# ModuleManHinhLCD1602.net
KiCad netlist of a schematic drawn in Altium Designer
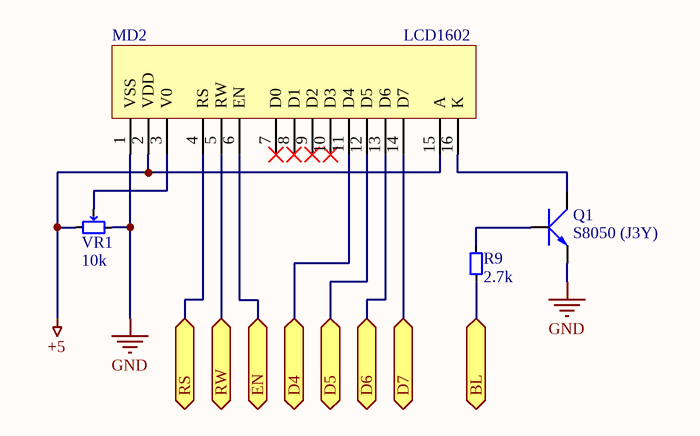
[diagram p0: ModuleManHinhLCD1602.SchDoc]

(export (version "E")
  (design (tool "Eeschema 10.0.6"))
  (components
    (comp (ref "MD2")
      (value "LCD1602")
      (footprint "LCD1602-A")
      (description "Module Man Hinh LCD1602")
      (libsource (lib "Module") (part "LCD1602"))
    )
    (comp (ref "Q1")
      (value "S8050 (J3Y)")
      (footprint "SOT23")
      (description "Transistor NPN 0.5A")
      (libsource (lib "phatvu1294_Lib") (part "S8050 (J3Y)"))
    )
    (comp (ref "R9")
      (value "2.7k")
      (footprint "R-0805")
      (description "Cac Loai Dien Tro")
      (libsource (lib "phatvu1294_Lib") (part "RES"))
    )
    (comp (ref "VR1")
      (value "10k")
      (footprint "VR-ADJ-3362P")
      (description "Cac Loai Bien Tro")
      (libsource (lib "phatvu1294_Lib") (part "VRES"))
    )
  )
  (nets
    (net (code "1") (name "+5") (class "Default")
      (node (ref "MD2") (pin "15") (pinfunction "A_15") (pintype "passive"))
      (node (ref "MD2") (pin "2") (pinfunction "VDD_2") (pintype "passive"))
      (node (ref "VR1") (pin "3") (pinfunction "3_3") (pintype "passive"))
    )
    (net (code "2") (name "/BL") (class "Default")
      (node (ref "R9") (pin "1") (pinfunction "1_1") (pintype "passive"))
    )
    (net (code "3") (name "/D4") (class "Default")
      (node (ref "MD2") (pin "11") (pinfunction "D4_11") (pintype "passive"))
    )
    (net (code "4") (name "/D5") (class "Default")
      (node (ref "MD2") (pin "12") (pinfunction "D5_12") (pintype "passive"))
    )
    (net (code "5") (name "/D6") (class "Default")
      (node (ref "MD2") (pin "13") (pinfunction "D6_13") (pintype "passive"))
    )
    (net (code "6") (name "/D7") (class "Default")
      (node (ref "MD2") (pin "14") (pinfunction "D7_14") (pintype "passive"))
    )
    (net (code "7") (name "/EN") (class "Default")
      (node (ref "MD2") (pin "6") (pinfunction "EN_6") (pintype "passive"))
    )
    (net (code "8") (name "/RS") (class "Default")
      (node (ref "MD2") (pin "4") (pinfunction "RS_4") (pintype "passive"))
    )
    (net (code "9") (name "/RW") (class "Default")
      (node (ref "MD2") (pin "5") (pinfunction "RW_5") (pintype "passive"))
    )
    (net (code "10") (name "GND") (class "Default")
      (node (ref "MD2") (pin "1") (pinfunction "VSS_1") (pintype "passive"))
      (node (ref "Q1") (pin "2") (pinfunction "E_2") (pintype "passive"))
      (node (ref "VR1") (pin "1") (pinfunction "1_1") (pintype "passive"))
    )
    (net (code "11") (name "Net-(MD2-K)") (class "Default")
      (node (ref "MD2") (pin "16") (pinfunction "K_16") (pintype "passive"))
      (node (ref "Q1") (pin "3") (pinfunction "C_3") (pintype "passive"))
    )
    (net (code "12") (name "Net-(MD2-V0)") (class "Default")
      (node (ref "MD2") (pin "3") (pinfunction "V0_3") (pintype "passive"))
      (node (ref "VR1") (pin "2") (pinfunction "2_2") (pintype "passive"))
    )
    (net (code "13") (name "Net-(Q1-B)") (class "Default")
      (node (ref "Q1") (pin "1") (pinfunction "B_1") (pintype "passive"))
      (node (ref "R9") (pin "2") (pinfunction "2_2") (pintype "passive"))
    )
    (net (code "14") (name "unconnected-(MD2-D0-Pad7)") (class "Default")
      (node (ref "MD2") (pin "7") (pinfunction "D0_7") (pintype "passive+no_connect"))
    )
    (net (code "15") (name "unconnected-(MD2-D1-Pad8)") (class "Default")
      (node (ref "MD2") (pin "8") (pinfunction "D1_8") (pintype "passive+no_connect"))
    )
    (net (code "16") (name "unconnected-(MD2-D2-Pad9)") (class "Default")
      (node (ref "MD2") (pin "9") (pinfunction "D2_9") (pintype "passive+no_connect"))
    )
    (net (code "17") (name "unconnected-(MD2-D3-Pad10)") (class "Default")
      (node (ref "MD2") (pin "10") (pinfunction "D3_10") (pintype "passive+no_connect"))
    )
  )
)
